# TXRobot-Boutons.net
KiCad netlist of a schematic drawn in Altium Designer
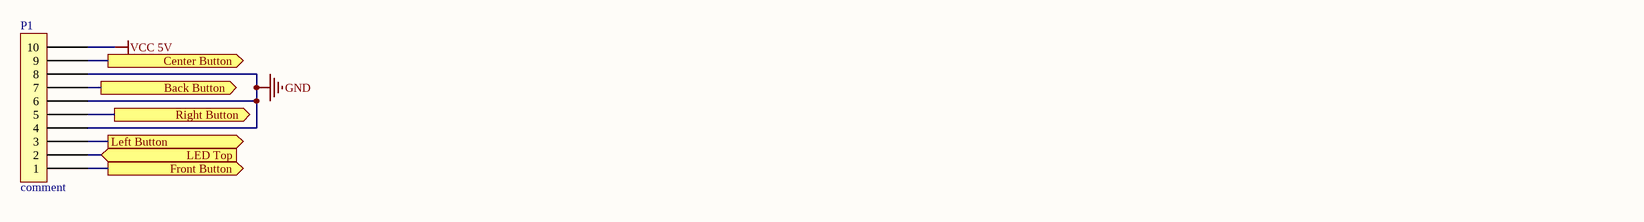
[diagram p0: TXRobot-Boutons.SchDoc]

(export (version "E")
  (design (tool "Eeschema 10.0.6"))
  (components
    (comp (ref "P1")
      (value "comment")
      (footprint "HE10-10V")
      (description "10-pin connector")
      (libsource (lib "ISEN_basics_26-05-2015") (part "HE10-10"))
    )
  )
  (nets
    (net (code "1") (name "/Back Button") (class "Default")
      (node (ref "P1") (pin "7") (pinfunction "7_7") (pintype "passive"))
    )
    (net (code "2") (name "/Center Button") (class "Default")
      (node (ref "P1") (pin "9") (pinfunction "9_9") (pintype "passive"))
    )
    (net (code "3") (name "/Front Button") (class "Default")
      (node (ref "P1") (pin "1") (pinfunction "1_1") (pintype "passive"))
    )
    (net (code "4") (name "/LED Top") (class "Default")
      (node (ref "P1") (pin "2") (pinfunction "2_2") (pintype "passive"))
    )
    (net (code "5") (name "/Left Button") (class "Default")
      (node (ref "P1") (pin "3") (pinfunction "3_3") (pintype "passive"))
    )
    (net (code "6") (name "/Right Button") (class "Default")
      (node (ref "P1") (pin "5") (pinfunction "5_5") (pintype "passive"))
    )
    (net (code "7") (name "GND") (class "Default")
      (node (ref "P1") (pin "4") (pinfunction "4_4") (pintype "passive"))
      (node (ref "P1") (pin "6") (pinfunction "6_6") (pintype "passive"))
      (node (ref "P1") (pin "8") (pinfunction "8_8") (pintype "passive"))
    )
    (net (code "8") (name "VCC 5V") (class "Default")
      (node (ref "P1") (pin "10") (pinfunction "10_10") (pintype "passive"))
    )
  )
)
